# SCH_enigma_2022-11-20.net
KiCad netlist of a schematic drawn in EasyEDA
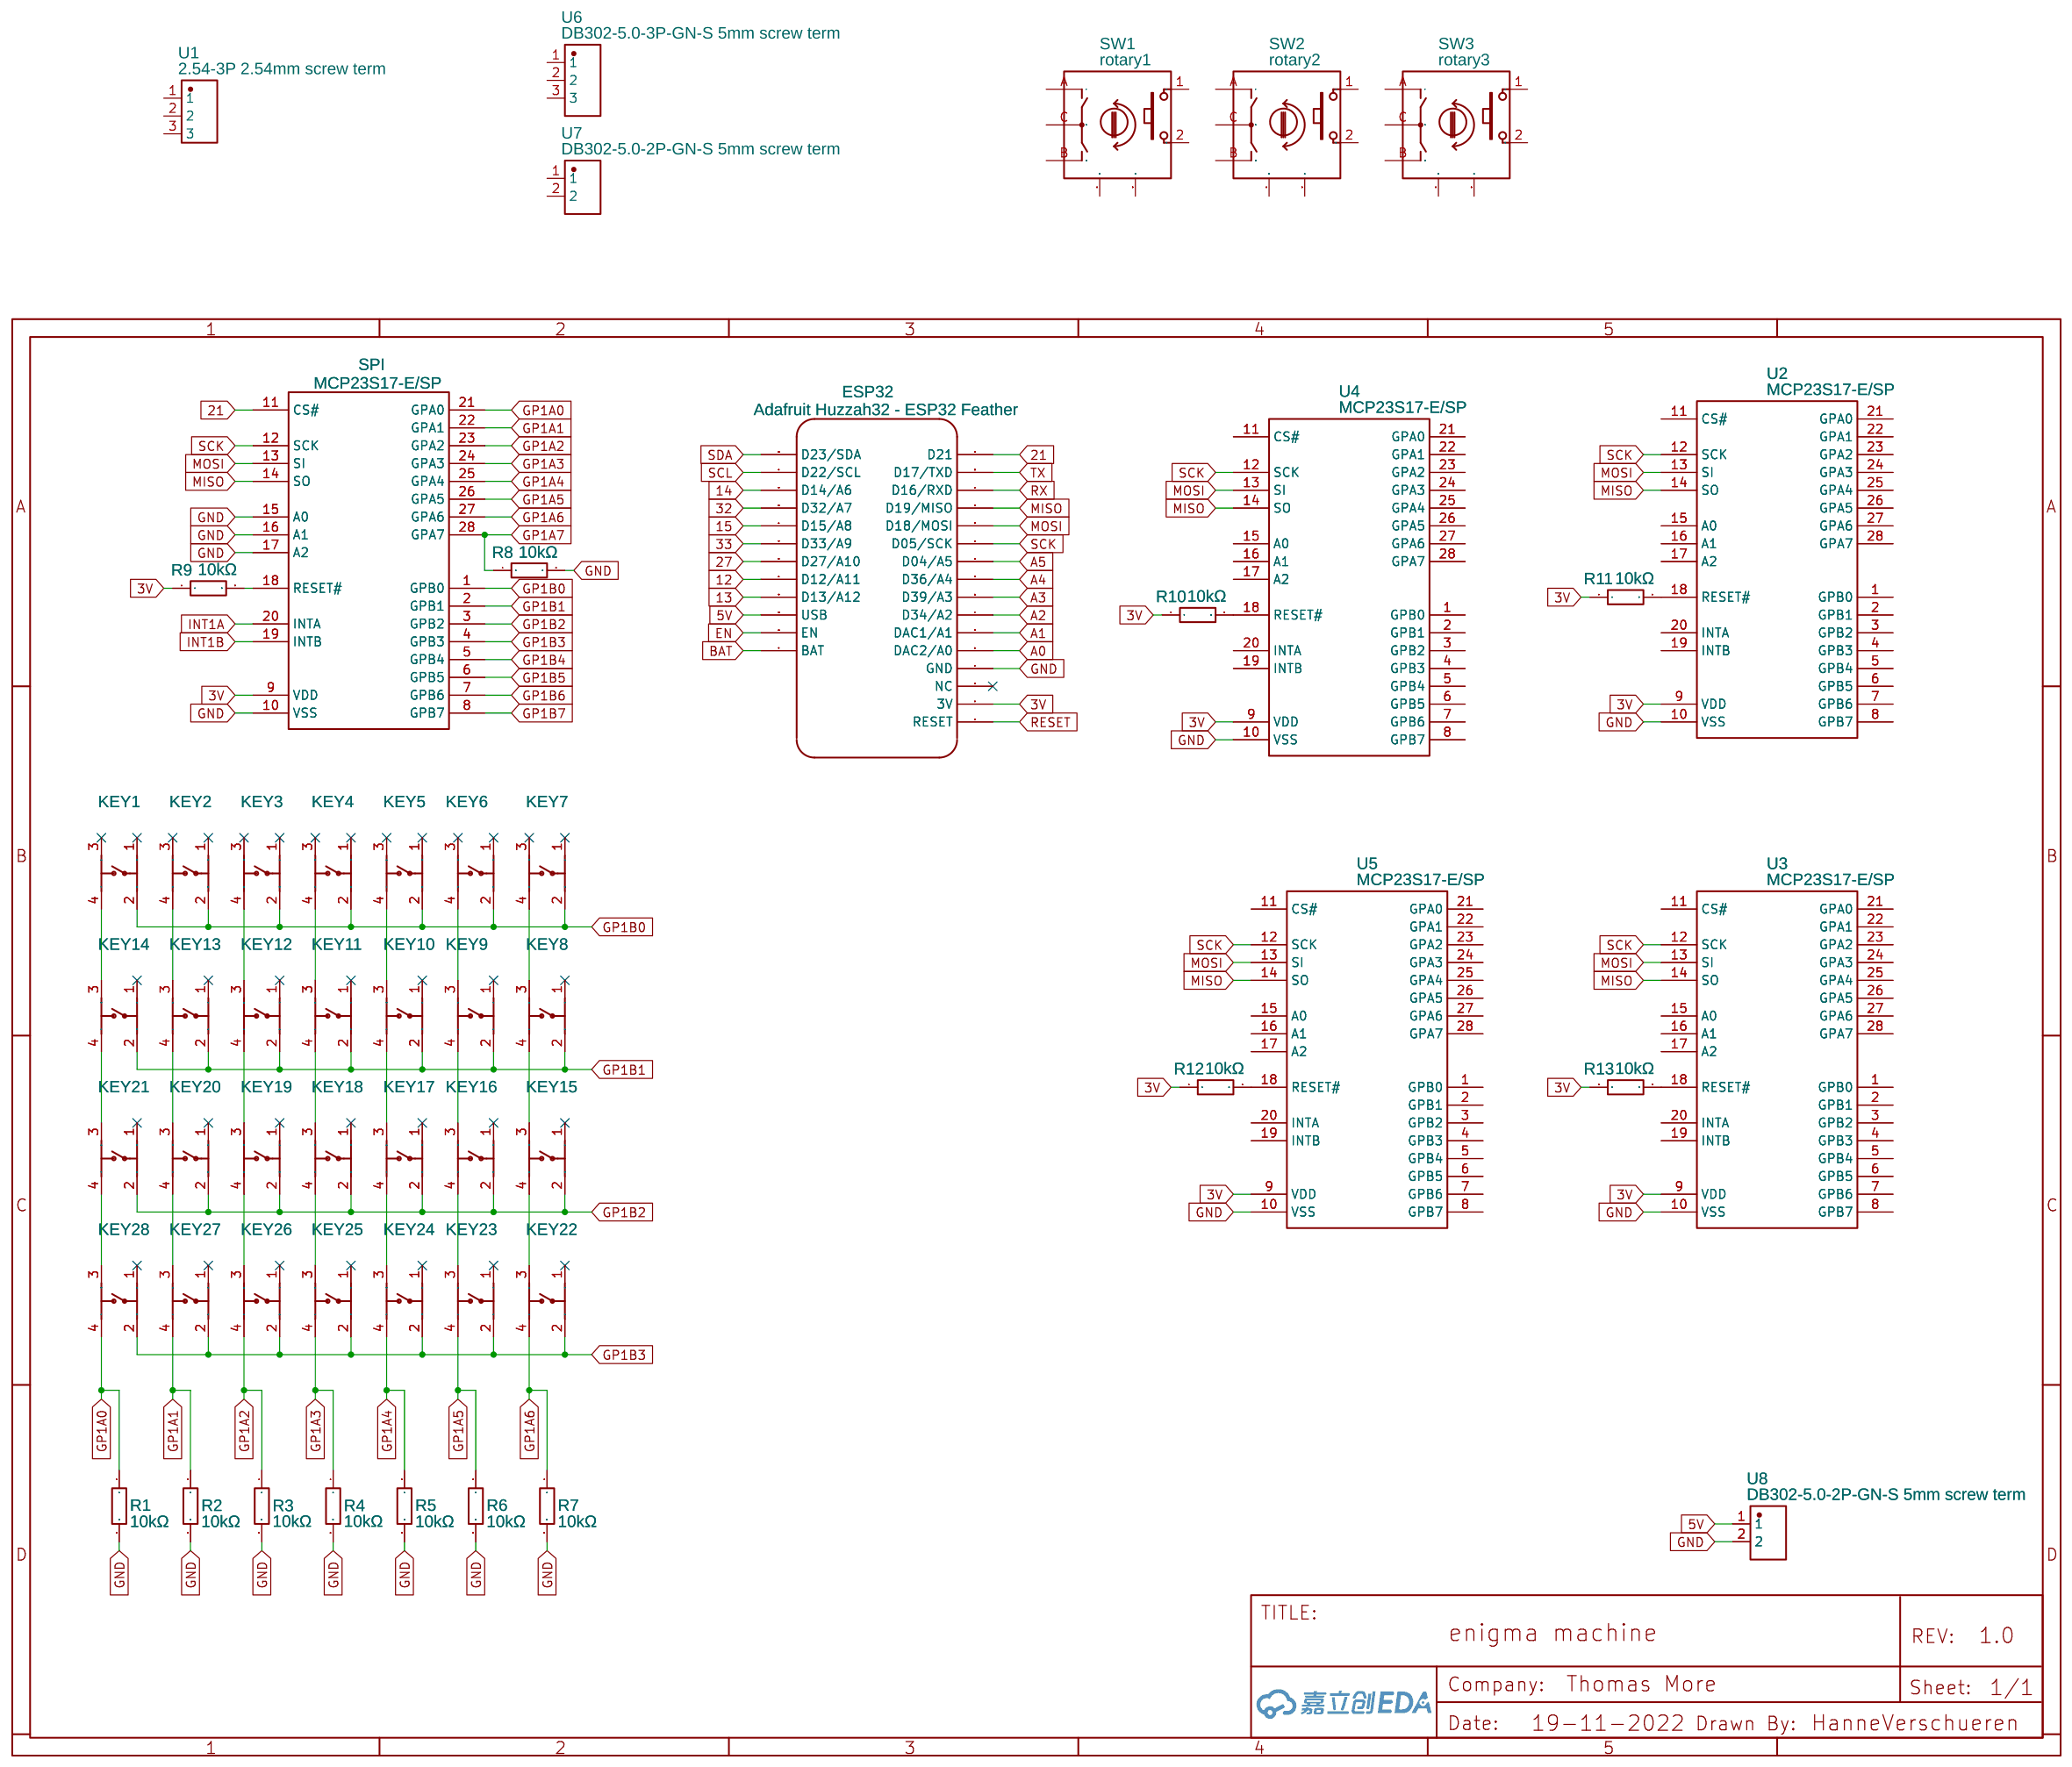
[diagram p0: schematic sheet]

(export (version "E")
  (design (tool "Eeschema 10.0.6"))
  (components
    (comp (ref "ESP32")
      (value "Adafruit Huzzah32 - ESP32 Feather")
      (fields (field (name "BOM_Manufacturer Part") "3405") (field (name "BOM_Supplier Part") "485-3405"))
      (libsource (lib "") (part "Adafruit Huzzah32 - ESP32 Feather"))
    )
    (comp (ref "KEY1")
      (value "12*12*7.3")
      (fields (field (name "BOM_Supplier Part") "C41103"))
      (libsource (lib "") (part "12*12*7.3"))
    )
    (comp (ref "KEY2")
      (value "12*12*7.3")
      (fields (field (name "BOM_Supplier Part") "C41103"))
      (libsource (lib "") (part "12*12*7.3"))
    )
    (comp (ref "KEY3")
      (value "12*12*7.3")
      (fields (field (name "BOM_Supplier Part") "C41103"))
      (libsource (lib "") (part "12*12*7.3"))
    )
    (comp (ref "KEY4")
      (value "12*12*7.3")
      (fields (field (name "BOM_Supplier Part") "C41103"))
      (libsource (lib "") (part "12*12*7.3"))
    )
    (comp (ref "KEY5")
      (value "12*12*7.3")
      (fields (field (name "BOM_Supplier Part") "C41103"))
      (libsource (lib "") (part "12*12*7.3"))
    )
    (comp (ref "KEY6")
      (value "12*12*7.3")
      (fields (field (name "BOM_Supplier Part") "C41103"))
      (libsource (lib "") (part "12*12*7.3"))
    )
    (comp (ref "KEY7")
      (value "12*12*7.3")
      (fields (field (name "BOM_Supplier Part") "C41103"))
      (libsource (lib "") (part "12*12*7.3"))
    )
    (comp (ref "KEY8")
      (value "12*12*7.3")
      (fields (field (name "BOM_Supplier Part") "C41103"))
      (libsource (lib "") (part "12*12*7.3"))
    )
    (comp (ref "KEY9")
      (value "12*12*7.3")
      (fields (field (name "BOM_Supplier Part") "C41103"))
      (libsource (lib "") (part "12*12*7.3"))
    )
    (comp (ref "KEY10")
      (value "12*12*7.3")
      (fields (field (name "BOM_Supplier Part") "C41103"))
      (libsource (lib "") (part "12*12*7.3"))
    )
    (comp (ref "KEY11")
      (value "12*12*7.3")
      (fields (field (name "BOM_Supplier Part") "C41103"))
      (libsource (lib "") (part "12*12*7.3"))
    )
    (comp (ref "KEY12")
      (value "12*12*7.3")
      (fields (field (name "BOM_Supplier Part") "C41103"))
      (libsource (lib "") (part "12*12*7.3"))
    )
    (comp (ref "KEY13")
      (value "12*12*7.3")
      (fields (field (name "BOM_Supplier Part") "C41103"))
      (libsource (lib "") (part "12*12*7.3"))
    )
    (comp (ref "KEY14")
      (value "12*12*7.3")
      (fields (field (name "BOM_Supplier Part") "C41103"))
      (libsource (lib "") (part "12*12*7.3"))
    )
    (comp (ref "KEY15")
      (value "12*12*7.3")
      (fields (field (name "BOM_Supplier Part") "C41103"))
      (libsource (lib "") (part "12*12*7.3"))
    )
    (comp (ref "KEY16")
      (value "12*12*7.3")
      (fields (field (name "BOM_Supplier Part") "C41103"))
      (libsource (lib "") (part "12*12*7.3"))
    )
    (comp (ref "KEY17")
      (value "12*12*7.3")
      (fields (field (name "BOM_Supplier Part") "C41103"))
      (libsource (lib "") (part "12*12*7.3"))
    )
    (comp (ref "KEY18")
      (value "12*12*7.3")
      (fields (field (name "BOM_Supplier Part") "C41103"))
      (libsource (lib "") (part "12*12*7.3"))
    )
    (comp (ref "KEY19")
      (value "12*12*7.3")
      (fields (field (name "BOM_Supplier Part") "C41103"))
      (libsource (lib "") (part "12*12*7.3"))
    )
    (comp (ref "KEY20")
      (value "12*12*7.3")
      (fields (field (name "BOM_Supplier Part") "C41103"))
      (libsource (lib "") (part "12*12*7.3"))
    )
    (comp (ref "KEY21")
      (value "12*12*7.3")
      (fields (field (name "BOM_Supplier Part") "C41103"))
      (libsource (lib "") (part "12*12*7.3"))
    )
    (comp (ref "KEY22")
      (value "12*12*7.3")
      (fields (field (name "BOM_Supplier Part") "C41103"))
      (libsource (lib "") (part "12*12*7.3"))
    )
    (comp (ref "KEY23")
      (value "12*12*7.3")
      (fields (field (name "BOM_Supplier Part") "C41103"))
      (libsource (lib "") (part "12*12*7.3"))
    )
    (comp (ref "KEY24")
      (value "12*12*7.3")
      (fields (field (name "BOM_Supplier Part") "C41103"))
      (libsource (lib "") (part "12*12*7.3"))
    )
    (comp (ref "KEY25")
      (value "12*12*7.3")
      (fields (field (name "BOM_Supplier Part") "C41103"))
      (libsource (lib "") (part "12*12*7.3"))
    )
    (comp (ref "KEY26")
      (value "12*12*7.3")
      (fields (field (name "BOM_Supplier Part") "C41103"))
      (libsource (lib "") (part "12*12*7.3"))
    )
    (comp (ref "KEY27")
      (value "12*12*7.3")
      (fields (field (name "BOM_Supplier Part") "C41103"))
      (libsource (lib "") (part "12*12*7.3"))
    )
    (comp (ref "KEY28")
      (value "12*12*7.3")
      (fields (field (name "BOM_Supplier Part") "C41103"))
      (libsource (lib "") (part "12*12*7.3"))
    )
    (comp (ref "R1")
      (value "10kΩ")
      (fields
        (field (name "BOM_Manufacturer Part") "RS-03K103JT")
        (field (name "BOM_Supplier Part") "C73809")
      )
      (libsource (lib "") (part "RS-03K103JT"))
    )
    (comp (ref "R2")
      (value "10kΩ")
      (fields
        (field (name "BOM_Manufacturer Part") "RS-03K103JT")
        (field (name "BOM_Supplier Part") "C73809")
      )
      (libsource (lib "") (part "RS-03K103JT"))
    )
    (comp (ref "R3")
      (value "10kΩ")
      (fields
        (field (name "BOM_Manufacturer Part") "RS-03K103JT")
        (field (name "BOM_Supplier Part") "C73809")
      )
      (libsource (lib "") (part "RS-03K103JT"))
    )
    (comp (ref "R4")
      (value "10kΩ")
      (fields
        (field (name "BOM_Manufacturer Part") "RS-03K103JT")
        (field (name "BOM_Supplier Part") "C73809")
      )
      (libsource (lib "") (part "RS-03K103JT"))
    )
    (comp (ref "R5")
      (value "10kΩ")
      (fields
        (field (name "BOM_Manufacturer Part") "RS-03K103JT")
        (field (name "BOM_Supplier Part") "C73809")
      )
      (libsource (lib "") (part "RS-03K103JT"))
    )
    (comp (ref "R6")
      (value "10kΩ")
      (fields
        (field (name "BOM_Manufacturer Part") "RS-03K103JT")
        (field (name "BOM_Supplier Part") "C73809")
      )
      (libsource (lib "") (part "RS-03K103JT"))
    )
    (comp (ref "R7")
      (value "10kΩ")
      (fields
        (field (name "BOM_Manufacturer Part") "RS-03K103JT")
        (field (name "BOM_Supplier Part") "C73809")
      )
      (libsource (lib "") (part "RS-03K103JT"))
    )
    (comp (ref "R8")
      (value "10kΩ")
      (fields
        (field (name "BOM_Manufacturer Part") "RS-03K103JT")
        (field (name "BOM_Supplier Part") "C73809")
      )
      (libsource (lib "") (part "RS-03K103JT_1"))
    )
    (comp (ref "R9")
      (value "10kΩ")
      (fields
        (field (name "BOM_Manufacturer Part") "RS-03K103JT")
        (field (name "BOM_Supplier Part") "C73809")
      )
      (libsource (lib "") (part "RS-03K103JT_1"))
    )
    (comp (ref "R10")
      (value "10kΩ")
      (fields
        (field (name "BOM_Manufacturer Part") "RS-03K103JT")
        (field (name "BOM_Supplier Part") "C73809")
      )
      (libsource (lib "") (part "RS-03K103JT_1"))
    )
    (comp (ref "R11")
      (value "10kΩ")
      (fields
        (field (name "BOM_Manufacturer Part") "RS-03K103JT")
        (field (name "BOM_Supplier Part") "C73809")
      )
      (libsource (lib "") (part "RS-03K103JT_1"))
    )
    (comp (ref "R12")
      (value "10kΩ")
      (fields
        (field (name "BOM_Manufacturer Part") "RS-03K103JT")
        (field (name "BOM_Supplier Part") "C73809")
      )
      (libsource (lib "") (part "RS-03K103JT_1"))
    )
    (comp (ref "R13")
      (value "10kΩ")
      (fields
        (field (name "BOM_Manufacturer Part") "RS-03K103JT")
        (field (name "BOM_Supplier Part") "C73809")
      )
      (libsource (lib "") (part "RS-03K103JT_1"))
    )
    (comp (ref "SPI")
      (value "MCP23S17-E/SP")
      (fields (field (name "BOM_Supplier Part") "C148096"))
      (libsource (lib "") (part "MCP23S17-E/SP_1"))
    )
    (comp (ref "SW1")
      (value "rotary1")
      (fields
        (field (name "BOM_Manufacturer Part") "PEC11R-4015F-S0024")
        (field (name "BOM_Supplier Part") "C143789")
      )
      (libsource (lib "") (part "PEC11R-4015F-S0024"))
    )
    (comp (ref "SW2")
      (value "rotary2")
      (fields
        (field (name "BOM_Manufacturer Part") "PEC11R-4015F-S0024")
        (field (name "BOM_Supplier Part") "C143789")
      )
      (libsource (lib "") (part "PEC11R-4015F-S0024"))
    )
    (comp (ref "SW3")
      (value "rotary3")
      (fields
        (field (name "BOM_Manufacturer Part") "PEC11R-4015F-S0024")
        (field (name "BOM_Supplier Part") "C143789")
      )
      (libsource (lib "") (part "PEC11R-4015F-S0024"))
    )
    (comp (ref "U1")
      (value "2.54-3P 2.54mm screw term")
      (fields
        (field (name "BOM_Manufacturer Part") "2.54-3P接线端子")
        (field (name "BOM_Supplier Part") "C68305")
      )
      (libsource (lib "") (part "2.54-3P"))
    )
    (comp (ref "U2")
      (value "MCP23S17-E/SP")
      (fields (field (name "BOM_Supplier Part") "C148096"))
      (libsource (lib "") (part "MCP23S17-E/SP"))
    )
    (comp (ref "U3")
      (value "MCP23S17-E/SP")
      (fields (field (name "BOM_Supplier Part") "C148096"))
      (libsource (lib "") (part "MCP23S17-E/SP"))
    )
    (comp (ref "U4")
      (value "MCP23S17-E/SP")
      (fields (field (name "BOM_Supplier Part") "C148096"))
      (libsource (lib "") (part "MCP23S17-E/SP"))
    )
    (comp (ref "U5")
      (value "MCP23S17-E/SP")
      (fields (field (name "BOM_Supplier Part") "C148096"))
      (libsource (lib "") (part "MCP23S17-E/SP"))
    )
    (comp (ref "U6")
      (value "DB302-5.0-3P-GN-S 5mm screw term")
      (fields
        (field (name "BOM_Manufacturer Part") "DB302-5.0-3P-GN-S")
        (field (name "BOM_Supplier Part") "C2997276")
      )
      (libsource (lib "") (part "DB302-5.0-3P-GN-S"))
    )
    (comp (ref "U7")
      (value "DB302-5.0-2P-GN-S 5mm screw term")
      (fields
        (field (name "BOM_Manufacturer Part") "DB302-5.0-2P-GN-S")
        (field (name "BOM_Supplier Part") "C2997275")
      )
      (libsource (lib "") (part "DB302-5.0-2P-GN-S"))
    )
    (comp (ref "U8")
      (value "DB302-5.0-2P-GN-S 5mm screw term")
      (fields
        (field (name "BOM_Manufacturer Part") "DB302-5.0-2P-GN-S")
        (field (name "BOM_Supplier Part") "C2997275")
      )
      (libsource (lib "") (part "DB302-5.0-2P-GN-S"))
    )
  )
  (nets
    (net (code "1") (name "3V") (class "Default")
      (node (ref "ESP32") (pin "2") (pinfunction "3V_2") (pintype "unspecified"))
      (node (ref "R10") (pin "1") (pinfunction "1_1") (pintype "input"))
      (node (ref "R11") (pin "1") (pinfunction "1_1") (pintype "input"))
      (node (ref "R12") (pin "1") (pinfunction "1_1") (pintype "input"))
      (node (ref "R13") (pin "1") (pinfunction "1_1") (pintype "input"))
      (node (ref "R9") (pin "1") (pinfunction "1_1") (pintype "input"))
      (node (ref "SPI") (pin "9") (pinfunction "VDD_9") (pintype "passive"))
      (node (ref "U2") (pin "9") (pinfunction "VDD_9") (pintype "passive"))
      (node (ref "U3") (pin "9") (pinfunction "VDD_9") (pintype "passive"))
      (node (ref "U4") (pin "9") (pinfunction "VDD_9") (pintype "passive"))
      (node (ref "U5") (pin "9") (pinfunction "VDD_9") (pintype "passive"))
    )
    (net (code "2") (name "5V") (class "Default")
      (node (ref "ESP32") (pin "19") (pinfunction "USB_19") (pintype "unspecified"))
      (node (ref "U8") (pin "1") (pinfunction "1_1") (pintype "unspecified"))
    )
    (net (code "3") (name "12") (class "Default")
      (node (ref "ESP32") (pin "21") (pinfunction "D12/A11_21") (pintype "unspecified"))
    )
    (net (code "4") (name "13") (class "Default")
      (node (ref "ESP32") (pin "20") (pinfunction "D13/A12_20") (pintype "unspecified"))
    )
    (net (code "5") (name "14") (class "Default")
      (node (ref "ESP32") (pin "26") (pinfunction "D14/A6_26") (pintype "unspecified"))
    )
    (net (code "6") (name "15") (class "Default")
      (node (ref "ESP32") (pin "24") (pinfunction "D15/A8_24") (pintype "unspecified"))
    )
    (net (code "7") (name "21") (class "Default")
      (node (ref "ESP32") (pin "16") (pinfunction "D21_16") (pintype "unspecified"))
      (node (ref "SPI") (pin "11") (pinfunction "CS#_11") (pintype "unspecified"))
    )
    (net (code "8") (name "27") (class "Default")
      (node (ref "ESP32") (pin "22") (pinfunction "D27/A10_22") (pintype "unspecified"))
    )
    (net (code "9") (name "32") (class "Default")
      (node (ref "ESP32") (pin "25") (pinfunction "D32/A7_25") (pintype "unspecified"))
    )
    (net (code "10") (name "33") (class "Default")
      (node (ref "ESP32") (pin "23") (pinfunction "D33/A9_23") (pintype "unspecified"))
    )
    (net (code "11") (name "A0") (class "Default")
      (node (ref "ESP32") (pin "5") (pinfunction "DAC2/A0_5") (pintype "unspecified"))
    )
    (net (code "12") (name "A1") (class "Default")
      (node (ref "ESP32") (pin "6") (pinfunction "DAC1/A1_6") (pintype "unspecified"))
    )
    (net (code "13") (name "A2") (class "Default")
      (node (ref "ESP32") (pin "7") (pinfunction "D34/A2_7") (pintype "unspecified"))
    )
    (net (code "14") (name "A3") (class "Default")
      (node (ref "ESP32") (pin "8") (pinfunction "D39/A3_8") (pintype "unspecified"))
    )
    (net (code "15") (name "A4") (class "Default")
      (node (ref "ESP32") (pin "9") (pinfunction "D36/A4_9") (pintype "unspecified"))
    )
    (net (code "16") (name "A5") (class "Default")
      (node (ref "ESP32") (pin "10") (pinfunction "D04/A5_10") (pintype "unspecified"))
    )
    (net (code "17") (name "BAT") (class "Default")
      (node (ref "ESP32") (pin "17") (pinfunction "BAT_17") (pintype "unspecified"))
    )
    (net (code "18") (name "EN") (class "Default")
      (node (ref "ESP32") (pin "18") (pinfunction "EN_18") (pintype "unspecified"))
    )
    (net (code "19") (name "GND") (class "Default")
      (node (ref "ESP32") (pin "4") (pinfunction "GND_4") (pintype "unspecified"))
      (node (ref "R1") (pin "2") (pinfunction "2_2") (pintype "input"))
      (node (ref "R2") (pin "2") (pinfunction "2_2") (pintype "input"))
      (node (ref "R3") (pin "2") (pinfunction "2_2") (pintype "input"))
      (node (ref "R4") (pin "2") (pinfunction "2_2") (pintype "input"))
      (node (ref "R5") (pin "2") (pinfunction "2_2") (pintype "input"))
      (node (ref "R6") (pin "2") (pinfunction "2_2") (pintype "input"))
      (node (ref "R7") (pin "2") (pinfunction "2_2") (pintype "input"))
      (node (ref "R8") (pin "2") (pinfunction "2_2") (pintype "input"))
      (node (ref "SPI") (pin "10") (pinfunction "VSS_10") (pintype "passive"))
      (node (ref "SPI") (pin "15") (pinfunction "A0_15") (pintype "unspecified"))
      (node (ref "SPI") (pin "16") (pinfunction "A1_16") (pintype "unspecified"))
      (node (ref "SPI") (pin "17") (pinfunction "A2_17") (pintype "unspecified"))
      (node (ref "U2") (pin "10") (pinfunction "VSS_10") (pintype "passive"))
      (node (ref "U3") (pin "10") (pinfunction "VSS_10") (pintype "passive"))
      (node (ref "U4") (pin "10") (pinfunction "VSS_10") (pintype "passive"))
      (node (ref "U5") (pin "10") (pinfunction "VSS_10") (pintype "passive"))
      (node (ref "U8") (pin "2") (pinfunction "2_2") (pintype "unspecified"))
    )
    (net (code "20") (name "GP1A0") (class "Default")
      (node (ref "KEY28") (pin "4") (pinfunction "4_4") (pintype "unspecified"))
      (node (ref "R1") (pin "1") (pinfunction "1_1") (pintype "input"))
      (node (ref "SPI") (pin "21") (pinfunction "GPA0_21") (pintype "bidirectional"))
    )
    (net (code "21") (name "GP1A1") (class "Default")
      (node (ref "KEY27") (pin "4") (pinfunction "4_4") (pintype "unspecified"))
      (node (ref "R2") (pin "1") (pinfunction "1_1") (pintype "input"))
      (node (ref "SPI") (pin "22") (pinfunction "GPA1_22") (pintype "bidirectional"))
    )
    (net (code "22") (name "GP1A2") (class "Default")
      (node (ref "KEY26") (pin "4") (pinfunction "4_4") (pintype "unspecified"))
      (node (ref "R3") (pin "1") (pinfunction "1_1") (pintype "input"))
      (node (ref "SPI") (pin "23") (pinfunction "GPA2_23") (pintype "bidirectional"))
    )
    (net (code "23") (name "GP1A3") (class "Default")
      (node (ref "KEY25") (pin "4") (pinfunction "4_4") (pintype "unspecified"))
      (node (ref "R4") (pin "1") (pinfunction "1_1") (pintype "input"))
      (node (ref "SPI") (pin "24") (pinfunction "GPA3_24") (pintype "bidirectional"))
    )
    (net (code "24") (name "GP1A4") (class "Default")
      (node (ref "KEY24") (pin "4") (pinfunction "4_4") (pintype "unspecified"))
      (node (ref "R5") (pin "1") (pinfunction "1_1") (pintype "input"))
      (node (ref "SPI") (pin "25") (pinfunction "GPA4_25") (pintype "bidirectional"))
    )
    (net (code "25") (name "GP1A5") (class "Default")
      (node (ref "KEY23") (pin "4") (pinfunction "4_4") (pintype "unspecified"))
      (node (ref "R6") (pin "1") (pinfunction "1_1") (pintype "input"))
      (node (ref "SPI") (pin "26") (pinfunction "GPA5_26") (pintype "bidirectional"))
    )
    (net (code "26") (name "GP1A6") (class "Default")
      (node (ref "KEY22") (pin "4") (pinfunction "4_4") (pintype "unspecified"))
      (node (ref "R7") (pin "1") (pinfunction "1_1") (pintype "input"))
      (node (ref "SPI") (pin "27") (pinfunction "GPA6_27") (pintype "bidirectional"))
    )
    (net (code "27") (name "GP1A7") (class "Default")
      (node (ref "R8") (pin "1") (pinfunction "1_1") (pintype "input"))
      (node (ref "SPI") (pin "28") (pinfunction "GPA7_28") (pintype "bidirectional"))
    )
    (net (code "28") (name "GP1B0") (class "Default")
      (node (ref "KEY1") (pin "2") (pinfunction "2_2") (pintype "unspecified"))
      (node (ref "KEY2") (pin "2") (pinfunction "2_2") (pintype "unspecified"))
      (node (ref "KEY3") (pin "2") (pinfunction "2_2") (pintype "unspecified"))
      (node (ref "KEY4") (pin "2") (pinfunction "2_2") (pintype "unspecified"))
      (node (ref "KEY5") (pin "2") (pinfunction "2_2") (pintype "unspecified"))
      (node (ref "KEY6") (pin "2") (pinfunction "2_2") (pintype "unspecified"))
      (node (ref "KEY7") (pin "2") (pinfunction "2_2") (pintype "unspecified"))
      (node (ref "SPI") (pin "1") (pinfunction "GPB0_1") (pintype "bidirectional"))
    )
    (net (code "29") (name "GP1B1") (class "Default")
      (node (ref "KEY10") (pin "2") (pinfunction "2_2") (pintype "unspecified"))
      (node (ref "KEY11") (pin "2") (pinfunction "2_2") (pintype "unspecified"))
      (node (ref "KEY12") (pin "2") (pinfunction "2_2") (pintype "unspecified"))
      (node (ref "KEY13") (pin "2") (pinfunction "2_2") (pintype "unspecified"))
      (node (ref "KEY14") (pin "2") (pinfunction "2_2") (pintype "unspecified"))
      (node (ref "KEY8") (pin "2") (pinfunction "2_2") (pintype "unspecified"))
      (node (ref "KEY9") (pin "2") (pinfunction "2_2") (pintype "unspecified"))
      (node (ref "SPI") (pin "2") (pinfunction "GPB1_2") (pintype "bidirectional"))
    )
    (net (code "30") (name "GP1B2") (class "Default")
      (node (ref "KEY15") (pin "2") (pinfunction "2_2") (pintype "unspecified"))
      (node (ref "KEY16") (pin "2") (pinfunction "2_2") (pintype "unspecified"))
      (node (ref "KEY17") (pin "2") (pinfunction "2_2") (pintype "unspecified"))
      (node (ref "KEY18") (pin "2") (pinfunction "2_2") (pintype "unspecified"))
      (node (ref "KEY19") (pin "2") (pinfunction "2_2") (pintype "unspecified"))
      (node (ref "KEY20") (pin "2") (pinfunction "2_2") (pintype "unspecified"))
      (node (ref "KEY21") (pin "2") (pinfunction "2_2") (pintype "unspecified"))
      (node (ref "SPI") (pin "3") (pinfunction "GPB2_3") (pintype "bidirectional"))
    )
    (net (code "31") (name "GP1B3") (class "Default")
      (node (ref "KEY22") (pin "2") (pinfunction "2_2") (pintype "unspecified"))
      (node (ref "KEY23") (pin "2") (pinfunction "2_2") (pintype "unspecified"))
      (node (ref "KEY24") (pin "2") (pinfunction "2_2") (pintype "unspecified"))
      (node (ref "KEY25") (pin "2") (pinfunction "2_2") (pintype "unspecified"))
      (node (ref "KEY26") (pin "2") (pinfunction "2_2") (pintype "unspecified"))
      (node (ref "KEY27") (pin "2") (pinfunction "2_2") (pintype "unspecified"))
      (node (ref "KEY28") (pin "2") (pinfunction "2_2") (pintype "unspecified"))
      (node (ref "SPI") (pin "4") (pinfunction "GPB3_4") (pintype "bidirectional"))
    )
    (net (code "32") (name "GP1B4") (class "Default")
      (node (ref "SPI") (pin "5") (pinfunction "GPB4_5") (pintype "bidirectional"))
    )
    (net (code "33") (name "GP1B5") (class "Default")
      (node (ref "SPI") (pin "6") (pinfunction "GPB5_6") (pintype "bidirectional"))
    )
    (net (code "34") (name "GP1B6") (class "Default")
      (node (ref "SPI") (pin "7") (pinfunction "GPB6_7") (pintype "bidirectional"))
    )
    (net (code "35") (name "GP1B7") (class "Default")
      (node (ref "SPI") (pin "8") (pinfunction "GPB7_8") (pintype "bidirectional"))
    )
    (net (code "36") (name "INT1A") (class "Default")
      (node (ref "SPI") (pin "20") (pinfunction "INTA_20") (pintype "unspecified"))
    )
    (net (code "37") (name "INT1B") (class "Default")
      (node (ref "SPI") (pin "19") (pinfunction "INTB_19") (pintype "unspecified"))
    )
    (net (code "38") (name "MISO") (class "Default")
      (node (ref "ESP32") (pin "13") (pinfunction "D19/MISO_13") (pintype "unspecified"))
      (node (ref "SPI") (pin "14") (pinfunction "SO_14") (pintype "unspecified"))
      (node (ref "U2") (pin "14") (pinfunction "SO_14") (pintype "unspecified"))
      (node (ref "U3") (pin "14") (pinfunction "SO_14") (pintype "unspecified"))
      (node (ref "U4") (pin "14") (pinfunction "SO_14") (pintype "unspecified"))
      (node (ref "U5") (pin "14") (pinfunction "SO_14") (pintype "unspecified"))
    )
    (net (code "39") (name "MOSI") (class "Default")
      (node (ref "ESP32") (pin "12") (pinfunction "D18/MOSI_12") (pintype "unspecified"))
      (node (ref "SPI") (pin "13") (pinfunction "SI_13") (pintype "unspecified"))
      (node (ref "U2") (pin "13") (pinfunction "SI_13") (pintype "unspecified"))
      (node (ref "U3") (pin "13") (pinfunction "SI_13") (pintype "unspecified"))
      (node (ref "U4") (pin "13") (pinfunction "SI_13") (pintype "unspecified"))
      (node (ref "U5") (pin "13") (pinfunction "SI_13") (pintype "unspecified"))
    )
    (net (code "40") (name "Net-(KEY1-Pad4)") (class "Default")
      (node (ref "KEY1") (pin "4") (pinfunction "4_4") (pintype "unspecified"))
      (node (ref "KEY14") (pin "3") (pinfunction "3_3") (pintype "unspecified"))
    )
    (net (code "41") (name "Net-(KEY6-Pad4)") (class "Default")
      (node (ref "KEY6") (pin "4") (pinfunction "4_4") (pintype "unspecified"))
      (node (ref "KEY9") (pin "3") (pinfunction "3_3") (pintype "unspecified"))
    )
    (net (code "42") (name "Net-(KEY7-Pad4)") (class "Default")
      (node (ref "KEY7") (pin "4") (pinfunction "4_4") (pintype "unspecified"))
      (node (ref "KEY8") (pin "3") (pinfunction "3_3") (pintype "unspecified"))
    )
    (net (code "43") (name "Net-(KEY10-Pad3)") (class "Default")
      (node (ref "KEY10") (pin "3") (pinfunction "3_3") (pintype "unspecified"))
      (node (ref "KEY5") (pin "4") (pinfunction "4_4") (pintype "unspecified"))
    )
    (net (code "44") (name "Net-(KEY10-Pad4)") (class "Default")
      (node (ref "KEY10") (pin "4") (pinfunction "4_4") (pintype "unspecified"))
      (node (ref "KEY17") (pin "3") (pinfunction "3_3") (pintype "unspecified"))
    )
    (net (code "45") (name "Net-(KEY11-Pad3)") (class "Default")
      (node (ref "KEY11") (pin "3") (pinfunction "3_3") (pintype "unspecified"))
      (node (ref "KEY4") (pin "4") (pinfunction "4_4") (pintype "unspecified"))
    )
    (net (code "46") (name "Net-(KEY11-Pad4)") (class "Default")
      (node (ref "KEY11") (pin "4") (pinfunction "4_4") (pintype "unspecified"))
      (node (ref "KEY18") (pin "3") (pinfunction "3_3") (pintype "unspecified"))
    )
    (net (code "47") (name "Net-(KEY12-Pad3)") (class "Default")
      (node (ref "KEY12") (pin "3") (pinfunction "3_3") (pintype "unspecified"))
      (node (ref "KEY3") (pin "4") (pinfunction "4_4") (pintype "unspecified"))
    )
    (net (code "48") (name "Net-(KEY12-Pad4)") (class "Default")
      (node (ref "KEY12") (pin "4") (pinfunction "4_4") (pintype "unspecified"))
      (node (ref "KEY19") (pin "3") (pinfunction "3_3") (pintype "unspecified"))
    )
    (net (code "49") (name "Net-(KEY13-Pad3)") (class "Default")
      (node (ref "KEY13") (pin "3") (pinfunction "3_3") (pintype "unspecified"))
      (node (ref "KEY2") (pin "4") (pinfunction "4_4") (pintype "unspecified"))
    )
    (net (code "50") (name "Net-(KEY13-Pad4)") (class "Default")
      (node (ref "KEY13") (pin "4") (pinfunction "4_4") (pintype "unspecified"))
      (node (ref "KEY20") (pin "3") (pinfunction "3_3") (pintype "unspecified"))
    )
    (net (code "51") (name "Net-(KEY14-Pad4)") (class "Default")
      (node (ref "KEY14") (pin "4") (pinfunction "4_4") (pintype "unspecified"))
      (node (ref "KEY21") (pin "3") (pinfunction "3_3") (pintype "unspecified"))
    )
    (net (code "52") (name "Net-(KEY15-Pad3)") (class "Default")
      (node (ref "KEY15") (pin "3") (pinfunction "3_3") (pintype "unspecified"))
      (node (ref "KEY8") (pin "4") (pinfunction "4_4") (pintype "unspecified"))
    )
    (net (code "53") (name "Net-(KEY15-Pad4)") (class "Default")
      (node (ref "KEY15") (pin "4") (pinfunction "4_4") (pintype "unspecified"))
      (node (ref "KEY22") (pin "3") (pinfunction "3_3") (pintype "unspecified"))
    )
    (net (code "54") (name "Net-(KEY16-Pad3)") (class "Default")
      (node (ref "KEY16") (pin "3") (pinfunction "3_3") (pintype "unspecified"))
      (node (ref "KEY9") (pin "4") (pinfunction "4_4") (pintype "unspecified"))
    )
    (net (code "55") (name "Net-(KEY16-Pad4)") (class "Default")
      (node (ref "KEY16") (pin "4") (pinfunction "4_4") (pintype "unspecified"))
      (node (ref "KEY23") (pin "3") (pinfunction "3_3") (pintype "unspecified"))
    )
    (net (code "56") (name "Net-(KEY17-Pad4)") (class "Default")
      (node (ref "KEY17") (pin "4") (pinfunction "4_4") (pintype "unspecified"))
      (node (ref "KEY24") (pin "3") (pinfunction "3_3") (pintype "unspecified"))
    )
    (net (code "57") (name "Net-(KEY18-Pad4)") (class "Default")
      (node (ref "KEY18") (pin "4") (pinfunction "4_4") (pintype "unspecified"))
      (node (ref "KEY25") (pin "3") (pinfunction "3_3") (pintype "unspecified"))
    )
    (net (code "58") (name "Net-(KEY19-Pad4)") (class "Default")
      (node (ref "KEY19") (pin "4") (pinfunction "4_4") (pintype "unspecified"))
      (node (ref "KEY26") (pin "3") (pinfunction "3_3") (pintype "unspecified"))
    )
    (net (code "59") (name "Net-(KEY20-Pad4)") (class "Default")
      (node (ref "KEY20") (pin "4") (pinfunction "4_4") (pintype "unspecified"))
      (node (ref "KEY27") (pin "3") (pinfunction "3_3") (pintype "unspecified"))
    )
    (net (code "60") (name "Net-(KEY21-Pad4)") (class "Default")
      (node (ref "KEY21") (pin "4") (pinfunction "4_4") (pintype "unspecified"))
      (node (ref "KEY28") (pin "3") (pinfunction "3_3") (pintype "unspecified"))
    )
    (net (code "61") (name "Net-(SPI-RESET#)") (class "Default")
      (node (ref "R9") (pin "2") (pinfunction "2_2") (pintype "input"))
      (node (ref "SPI") (pin "18") (pinfunction "RESET#_18") (pintype "unspecified"))
    )
    (net (code "62") (name "Net-(U2-RESET#)") (class "Default")
      (node (ref "R11") (pin "2") (pinfunction "2_2") (pintype "input"))
      (node (ref "U2") (pin "18") (pinfunction "RESET#_18") (pintype "unspecified"))
    )
    (net (code "63") (name "Net-(U3-RESET#)") (class "Default")
      (node (ref "R13") (pin "2") (pinfunction "2_2") (pintype "input"))
      (node (ref "U3") (pin "18") (pinfunction "RESET#_18") (pintype "unspecified"))
    )
    (net (code "64") (name "Net-(U4-RESET#)") (class "Default")
      (node (ref "R10") (pin "2") (pinfunction "2_2") (pintype "input"))
      (node (ref "U4") (pin "18") (pinfunction "RESET#_18") (pintype "unspecified"))
    )
    (net (code "65") (name "Net-(U5-RESET#)") (class "Default")
      (node (ref "R12") (pin "2") (pinfunction "2_2") (pintype "input"))
      (node (ref "U5") (pin "18") (pinfunction "RESET#_18") (pintype "unspecified"))
    )
    (net (code "66") (name "RESET") (class "Default")
      (node (ref "ESP32") (pin "1") (pinfunction "RESET_1") (pintype "unspecified"))
    )
    (net (code "67") (name "RX") (class "Default")
      (node (ref "ESP32") (pin "14") (pinfunction "D16/RXD_14") (pintype "unspecified"))
    )
    (net (code "68") (name "SCK") (class "Default")
      (node (ref "ESP32") (pin "11") (pinfunction "D05/SCK_11") (pintype "unspecified"))
      (node (ref "SPI") (pin "12") (pinfunction "SCK_12") (pintype "unspecified"))
      (node (ref "U2") (pin "12") (pinfunction "SCK_12") (pintype "unspecified"))
      (node (ref "U3") (pin "12") (pinfunction "SCK_12") (pintype "unspecified"))
      (node (ref "U4") (pin "12") (pinfunction "SCK_12") (pintype "unspecified"))
      (node (ref "U5") (pin "12") (pinfunction "SCK_12") (pintype "unspecified"))
    )
    (net (code "69") (name "SCL") (class "Default")
      (node (ref "ESP32") (pin "27") (pinfunction "D22/SCL_27") (pintype "unspecified"))
    )
    (net (code "70") (name "SDA") (class "Default")
      (node (ref "ESP32") (pin "28") (pinfunction "D23/SDA_28") (pintype "unspecified"))
    )
    (net (code "71") (name "TX") (class "Default")
      (node (ref "ESP32") (pin "15") (pinfunction "D17/TXD_15") (pintype "unspecified"))
    )
    (net (code "72") (name "unconnected-(ESP32-NC-Pad3)") (class "Default")
      (node (ref "ESP32") (pin "3") (pinfunction "NC_3") (pintype "unspecified+no_connect"))
    )
    (net (code "73") (name "unconnected-(KEY1-Pad1)") (class "Default")
      (node (ref "KEY1") (pin "1") (pinfunction "1_1") (pintype "unspecified+no_connect"))
    )
    (net (code "74") (name "unconnected-(KEY1-Pad3)") (class "Default")
      (node (ref "KEY1") (pin "3") (pinfunction "3_3") (pintype "unspecified+no_connect"))
    )
    (net (code "75") (name "unconnected-(KEY2-Pad1)") (class "Default")
      (node (ref "KEY2") (pin "1") (pinfunction "1_1") (pintype "unspecified+no_connect"))
    )
    (net (code "76") (name "unconnected-(KEY2-Pad3)") (class "Default")
      (node (ref "KEY2") (pin "3") (pinfunction "3_3") (pintype "unspecified+no_connect"))
    )
    (net (code "77") (name "unconnected-(KEY3-Pad1)") (class "Default")
      (node (ref "KEY3") (pin "1") (pinfunction "1_1") (pintype "unspecified+no_connect"))
    )
    (net (code "78") (name "unconnected-(KEY3-Pad3)") (class "Default")
      (node (ref "KEY3") (pin "3") (pinfunction "3_3") (pintype "unspecified+no_connect"))
    )
    (net (code "79") (name "unconnected-(KEY4-Pad1)") (class "Default")
      (node (ref "KEY4") (pin "1") (pinfunction "1_1") (pintype "unspecified+no_connect"))
    )
    (net (code "80") (name "unconnected-(KEY4-Pad3)") (class "Default")
      (node (ref "KEY4") (pin "3") (pinfunction "3_3") (pintype "unspecified+no_connect"))
    )
    (net (code "81") (name "unconnected-(KEY5-Pad1)") (class "Default")
      (node (ref "KEY5") (pin "1") (pinfunction "1_1") (pintype "unspecified+no_connect"))
    )
    (net (code "82") (name "unconnected-(KEY5-Pad3)") (class "Default")
      (node (ref "KEY5") (pin "3") (pinfunction "3_3") (pintype "unspecified+no_connect"))
    )
    (net (code "83") (name "unconnected-(KEY6-Pad1)") (class "Default")
      (node (ref "KEY6") (pin "1") (pinfunction "1_1") (pintype "unspecified+no_connect"))
    )
    (net (code "84") (name "unconnected-(KEY6-Pad3)") (class "Default")
      (node (ref "KEY6") (pin "3") (pinfunction "3_3") (pintype "unspecified+no_connect"))
    )
    (net (code "85") (name "unconnected-(KEY7-Pad1)") (class "Default")
      (node (ref "KEY7") (pin "1") (pinfunction "1_1") (pintype "unspecified+no_connect"))
    )
    (net (code "86") (name "unconnected-(KEY7-Pad3)") (class "Default")
      (node (ref "KEY7") (pin "3") (pinfunction "3_3") (pintype "unspecified+no_connect"))
    )
    (net (code "87") (name "unconnected-(KEY8-Pad1)") (class "Default")
      (node (ref "KEY8") (pin "1") (pinfunction "1_1") (pintype "unspecified+no_connect"))
    )
    (net (code "88") (name "unconnected-(KEY9-Pad1)") (class "Default")
      (node (ref "KEY9") (pin "1") (pinfunction "1_1") (pintype "unspecified+no_connect"))
    )
    (net (code "89") (name "unconnected-(KEY10-Pad1)") (class "Default")
      (node (ref "KEY10") (pin "1") (pinfunction "1_1") (pintype "unspecified+no_connect"))
    )
    (net (code "90") (name "unconnected-(KEY11-Pad1)") (class "Default")
      (node (ref "KEY11") (pin "1") (pinfunction "1_1") (pintype "unspecified+no_connect"))
    )
    (net (code "91") (name "unconnected-(KEY12-Pad1)") (class "Default")
      (node (ref "KEY12") (pin "1") (pinfunction "1_1") (pintype "unspecified+no_connect"))
    )
    (net (code "92") (name "unconnected-(KEY13-Pad1)") (class "Default")
      (node (ref "KEY13") (pin "1") (pinfunction "1_1") (pintype "unspecified+no_connect"))
    )
    (net (code "93") (name "unconnected-(KEY14-Pad1)") (class "Default")
      (node (ref "KEY14") (pin "1") (pinfunction "1_1") (pintype "unspecified+no_connect"))
    )
    (net (code "94") (name "unconnected-(KEY15-Pad1)") (class "Default")
      (node (ref "KEY15") (pin "1") (pinfunction "1_1") (pintype "unspecified+no_connect"))
    )
    (net (code "95") (name "unconnected-(KEY16-Pad1)") (class "Default")
      (node (ref "KEY16") (pin "1") (pinfunction "1_1") (pintype "unspecified+no_connect"))
    )
    (net (code "96") (name "unconnected-(KEY17-Pad1)") (class "Default")
      (node (ref "KEY17") (pin "1") (pinfunction "1_1") (pintype "unspecified+no_connect"))
    )
    (net (code "97") (name "unconnected-(KEY18-Pad1)") (class "Default")
      (node (ref "KEY18") (pin "1") (pinfunction "1_1") (pintype "unspecified+no_connect"))
    )
    (net (code "98") (name "unconnected-(KEY19-Pad1)") (class "Default")
      (node (ref "KEY19") (pin "1") (pinfunction "1_1") (pintype "unspecified+no_connect"))
    )
    (net (code "99") (name "unconnected-(KEY20-Pad1)") (class "Default")
      (node (ref "KEY20") (pin "1") (pinfunction "1_1") (pintype "unspecified+no_connect"))
    )
    (net (code "100") (name "unconnected-(KEY21-Pad1)") (class "Default")
      (node (ref "KEY21") (pin "1") (pinfunction "1_1") (pintype "unspecified+no_connect"))
    )
    (net (code "101") (name "unconnected-(KEY22-Pad1)") (class "Default")
      (node (ref "KEY22") (pin "1") (pinfunction "1_1") (pintype "unspecified+no_connect"))
    )
    (net (code "102") (name "unconnected-(KEY23-Pad1)") (class "Default")
      (node (ref "KEY23") (pin "1") (pinfunction "1_1") (pintype "unspecified+no_connect"))
    )
    (net (code "103") (name "unconnected-(KEY24-Pad1)") (class "Default")
      (node (ref "KEY24") (pin "1") (pinfunction "1_1") (pintype "unspecified+no_connect"))
    )
    (net (code "104") (name "unconnected-(KEY25-Pad1)") (class "Default")
      (node (ref "KEY25") (pin "1") (pinfunction "1_1") (pintype "unspecified+no_connect"))
    )
    (net (code "105") (name "unconnected-(KEY26-Pad1)") (class "Default")
      (node (ref "KEY26") (pin "1") (pinfunction "1_1") (pintype "unspecified+no_connect"))
    )
    (net (code "106") (name "unconnected-(KEY27-Pad1)") (class "Default")
      (node (ref "KEY27") (pin "1") (pinfunction "1_1") (pintype "unspecified+no_connect"))
    )
    (net (code "107") (name "unconnected-(KEY28-Pad1)") (class "Default")
      (node (ref "KEY28") (pin "1") (pinfunction "1_1") (pintype "unspecified+no_connect"))
    )
    (net (code "108") (name "unconnected-(SW1-Pad1)") (class "Default")
      (node (ref "SW1") (pin "1") (pinfunction "1_1") (pintype "unspecified"))
    )
    (net (code "109") (name "unconnected-(SW1-Pad2)") (class "Default")
      (node (ref "SW1") (pin "2") (pinfunction "2_2") (pintype "unspecified"))
    )
    (net (code "110") (name "unconnected-(SW1-PadA)") (class "Default")
      (node (ref "SW1") (pin "A") (pinfunction "A_A") (pintype "unspecified"))
    )
    (net (code "111") (name "unconnected-(SW1-PadB)") (class "Default")
      (node (ref "SW1") (pin "B") (pinfunction "B_B") (pintype "unspecified"))
    )
    (net (code "112") (name "unconnected-(SW1-PadC)") (class "Default")
      (node (ref "SW1") (pin "C") (pinfunction "C_C") (pintype "unspecified"))
    )
    (net (code "113") (name "unconnected-(SW1-PadMT1)") (class "Default")
      (node (ref "SW1") (pin "MT1") (pinfunction "MT1_MT1") (pintype "unspecified"))
    )
    (net (code "114") (name "unconnected-(SW1-PadMT2)") (class "Default")
      (node (ref "SW1") (pin "MT2") (pinfunction "MT2_MT2") (pintype "unspecified"))
    )
    (net (code "115") (name "unconnected-(SW2-Pad1)") (class "Default")
      (node (ref "SW2") (pin "1") (pinfunction "1_1") (pintype "unspecified"))
    )
    (net (code "116") (name "unconnected-(SW2-Pad2)") (class "Default")
      (node (ref "SW2") (pin "2") (pinfunction "2_2") (pintype "unspecified"))
    )
    (net (code "117") (name "unconnected-(SW2-PadA)") (class "Default")
      (node (ref "SW2") (pin "A") (pinfunction "A_A") (pintype "unspecified"))
    )
    (net (code "118") (name "unconnected-(SW2-PadB)") (class "Default")
      (node (ref "SW2") (pin "B") (pinfunction "B_B") (pintype "unspecified"))
    )
    (net (code "119") (name "unconnected-(SW2-PadC)") (class "Default")
      (node (ref "SW2") (pin "C") (pinfunction "C_C") (pintype "unspecified"))
    )
    (net (code "120") (name "unconnected-(SW2-PadMT1)") (class "Default")
      (node (ref "SW2") (pin "MT1") (pinfunction "MT1_MT1") (pintype "unspecified"))
    )
    (net (code "121") (name "unconnected-(SW2-PadMT2)") (class "Default")
      (node (ref "SW2") (pin "MT2") (pinfunction "MT2_MT2") (pintype "unspecified"))
    )
    (net (code "122") (name "unconnected-(SW3-Pad1)") (class "Default")
      (node (ref "SW3") (pin "1") (pinfunction "1_1") (pintype "unspecified"))
    )
    (net (code "123") (name "unconnected-(SW3-Pad2)") (class "Default")
      (node (ref "SW3") (pin "2") (pinfunction "2_2") (pintype "unspecified"))
    )
    (net (code "124") (name "unconnected-(SW3-PadA)") (class "Default")
      (node (ref "SW3") (pin "A") (pinfunction "A_A") (pintype "unspecified"))
    )
    (net (code "125") (name "unconnected-(SW3-PadB)") (class "Default")
      (node (ref "SW3") (pin "B") (pinfunction "B_B") (pintype "unspecified"))
    )
    (net (code "126") (name "unconnected-(SW3-PadC)") (class "Default")
      (node (ref "SW3") (pin "C") (pinfunction "C_C") (pintype "unspecified"))
    )
    (net (code "127") (name "unconnected-(SW3-PadMT1)") (class "Default")
      (node (ref "SW3") (pin "MT1") (pinfunction "MT1_MT1") (pintype "unspecified"))
    )
    (net (code "128") (name "unconnected-(SW3-PadMT2)") (class "Default")
      (node (ref "SW3") (pin "MT2") (pinfunction "MT2_MT2") (pintype "unspecified"))
    )
    (net (code "129") (name "unconnected-(U1-Pad1)") (class "Default")
      (node (ref "U1") (pin "1") (pinfunction "1_1") (pintype "unspecified"))
    )
    (net (code "130") (name "unconnected-(U1-Pad2)") (class "Default")
      (node (ref "U1") (pin "2") (pinfunction "2_2") (pintype "unspecified"))
    )
    (net (code "131") (name "unconnected-(U1-Pad3)") (class "Default")
      (node (ref "U1") (pin "3") (pinfunction "3_3") (pintype "unspecified"))
    )
    (net (code "132") (name "unconnected-(U2-A0-Pad15)") (class "Default")
      (node (ref "U2") (pin "15") (pinfunction "A0_15") (pintype "unspecified"))
    )
    (net (code "133") (name "unconnected-(U2-A1-Pad16)") (class "Default")
      (node (ref "U2") (pin "16") (pinfunction "A1_16") (pintype "unspecified"))
    )
    (net (code "134") (name "unconnected-(U2-A2-Pad17)") (class "Default")
      (node (ref "U2") (pin "17") (pinfunction "A2_17") (pintype "unspecified"))
    )
    (net (code "135") (name "unconnected-(U2-CS#-Pad11)") (class "Default")
      (node (ref "U2") (pin "11") (pinfunction "CS#_11") (pintype "unspecified"))
    )
    (net (code "136") (name "unconnected-(U2-GPA0-Pad21)") (class "Default")
      (node (ref "U2") (pin "21") (pinfunction "GPA0_21") (pintype "bidirectional"))
    )
    (net (code "137") (name "unconnected-(U2-GPA1-Pad22)") (class "Default")
      (node (ref "U2") (pin "22") (pinfunction "GPA1_22") (pintype "bidirectional"))
    )
    (net (code "138") (name "unconnected-(U2-GPA2-Pad23)") (class "Default")
      (node (ref "U2") (pin "23") (pinfunction "GPA2_23") (pintype "bidirectional"))
    )
    (net (code "139") (name "unconnected-(U2-GPA3-Pad24)") (class "Default")
      (node (ref "U2") (pin "24") (pinfunction "GPA3_24") (pintype "bidirectional"))
    )
    (net (code "140") (name "unconnected-(U2-GPA4-Pad25)") (class "Default")
      (node (ref "U2") (pin "25") (pinfunction "GPA4_25") (pintype "bidirectional"))
    )
    (net (code "141") (name "unconnected-(U2-GPA5-Pad26)") (class "Default")
      (node (ref "U2") (pin "26") (pinfunction "GPA5_26") (pintype "bidirectional"))
    )
    (net (code "142") (name "unconnected-(U2-GPA6-Pad27)") (class "Default")
      (node (ref "U2") (pin "27") (pinfunction "GPA6_27") (pintype "bidirectional"))
    )
    (net (code "143") (name "unconnected-(U2-GPA7-Pad28)") (class "Default")
      (node (ref "U2") (pin "28") (pinfunction "GPA7_28") (pintype "bidirectional"))
    )
    (net (code "144") (name "unconnected-(U2-GPB0-Pad1)") (class "Default")
      (node (ref "U2") (pin "1") (pinfunction "GPB0_1") (pintype "bidirectional"))
    )
    (net (code "145") (name "unconnected-(U2-GPB1-Pad2)") (class "Default")
      (node (ref "U2") (pin "2") (pinfunction "GPB1_2") (pintype "bidirectional"))
    )
    (net (code "146") (name "unconnected-(U2-GPB2-Pad3)") (class "Default")
      (node (ref "U2") (pin "3") (pinfunction "GPB2_3") (pintype "bidirectional"))
    )
    (net (code "147") (name "unconnected-(U2-GPB3-Pad4)") (class "Default")
      (node (ref "U2") (pin "4") (pinfunction "GPB3_4") (pintype "bidirectional"))
    )
    (net (code "148") (name "unconnected-(U2-GPB4-Pad5)") (class "Default")
      (node (ref "U2") (pin "5") (pinfunction "GPB4_5") (pintype "bidirectional"))
    )
    (net (code "149") (name "unconnected-(U2-GPB5-Pad6)") (class "Default")
      (node (ref "U2") (pin "6") (pinfunction "GPB5_6") (pintype "bidirectional"))
    )
    (net (code "150") (name "unconnected-(U2-GPB6-Pad7)") (class "Default")
      (node (ref "U2") (pin "7") (pinfunction "GPB6_7") (pintype "bidirectional"))
    )
    (net (code "151") (name "unconnected-(U2-GPB7-Pad8)") (class "Default")
      (node (ref "U2") (pin "8") (pinfunction "GPB7_8") (pintype "bidirectional"))
    )
    (net (code "152") (name "unconnected-(U2-INTA-Pad20)") (class "Default")
      (node (ref "U2") (pin "20") (pinfunction "INTA_20") (pintype "unspecified"))
    )
    (net (code "153") (name "unconnected-(U2-INTB-Pad19)") (class "Default")
      (node (ref "U2") (pin "19") (pinfunction "INTB_19") (pintype "unspecified"))
    )
    (net (code "154") (name "unconnected-(U3-A0-Pad15)") (class "Default")
      (node (ref "U3") (pin "15") (pinfunction "A0_15") (pintype "unspecified"))
    )
    (net (code "155") (name "unconnected-(U3-A1-Pad16)") (class "Default")
      (node (ref "U3") (pin "16") (pinfunction "A1_16") (pintype "unspecified"))
    )
    (net (code "156") (name "unconnected-(U3-A2-Pad17)") (class "Default")
      (node (ref "U3") (pin "17") (pinfunction "A2_17") (pintype "unspecified"))
    )
    (net (code "157") (name "unconnected-(U3-CS#-Pad11)") (class "Default")
      (node (ref "U3") (pin "11") (pinfunction "CS#_11") (pintype "unspecified"))
    )
    (net (code "158") (name "unconnected-(U3-GPA0-Pad21)") (class "Default")
      (node (ref "U3") (pin "21") (pinfunction "GPA0_21") (pintype "bidirectional"))
    )
    (net (code "159") (name "unconnected-(U3-GPA1-Pad22)") (class "Default")
      (node (ref "U3") (pin "22") (pinfunction "GPA1_22") (pintype "bidirectional"))
    )
    (net (code "160") (name "unconnected-(U3-GPA2-Pad23)") (class "Default")
      (node (ref "U3") (pin "23") (pinfunction "GPA2_23") (pintype "bidirectional"))
    )
    (net (code "161") (name "unconnected-(U3-GPA3-Pad24)") (class "Default")
      (node (ref "U3") (pin "24") (pinfunction "GPA3_24") (pintype "bidirectional"))
    )
    (net (code "162") (name "unconnected-(U3-GPA4-Pad25)") (class "Default")
      (node (ref "U3") (pin "25") (pinfunction "GPA4_25") (pintype "bidirectional"))
    )
    (net (code "163") (name "unconnected-(U3-GPA5-Pad26)") (class "Default")
      (node (ref "U3") (pin "26") (pinfunction "GPA5_26") (pintype "bidirectional"))
    )
    (net (code "164") (name "unconnected-(U3-GPA6-Pad27)") (class "Default")
      (node (ref "U3") (pin "27") (pinfunction "GPA6_27") (pintype "bidirectional"))
    )
    (net (code "165") (name "unconnected-(U3-GPA7-Pad28)") (class "Default")
      (node (ref "U3") (pin "28") (pinfunction "GPA7_28") (pintype "bidirectional"))
    )
    (net (code "166") (name "unconnected-(U3-GPB0-Pad1)") (class "Default")
      (node (ref "U3") (pin "1") (pinfunction "GPB0_1") (pintype "bidirectional"))
    )
    (net (code "167") (name "unconnected-(U3-GPB1-Pad2)") (class "Default")
      (node (ref "U3") (pin "2") (pinfunction "GPB1_2") (pintype "bidirectional"))
    )
    (net (code "168") (name "unconnected-(U3-GPB2-Pad3)") (class "Default")
      (node (ref "U3") (pin "3") (pinfunction "GPB2_3") (pintype "bidirectional"))
    )
    (net (code "169") (name "unconnected-(U3-GPB3-Pad4)") (class "Default")
      (node (ref "U3") (pin "4") (pinfunction "GPB3_4") (pintype "bidirectional"))
    )
    (net (code "170") (name "unconnected-(U3-GPB4-Pad5)") (class "Default")
      (node (ref "U3") (pin "5") (pinfunction "GPB4_5") (pintype "bidirectional"))
    )
    (net (code "171") (name "unconnected-(U3-GPB5-Pad6)") (class "Default")
      (node (ref "U3") (pin "6") (pinfunction "GPB5_6") (pintype "bidirectional"))
    )
    (net (code "172") (name "unconnected-(U3-GPB6-Pad7)") (class "Default")
      (node (ref "U3") (pin "7") (pinfunction "GPB6_7") (pintype "bidirectional"))
    )
    (net (code "173") (name "unconnected-(U3-GPB7-Pad8)") (class "Default")
      (node (ref "U3") (pin "8") (pinfunction "GPB7_8") (pintype "bidirectional"))
    )
    (net (code "174") (name "unconnected-(U3-INTA-Pad20)") (class "Default")
      (node (ref "U3") (pin "20") (pinfunction "INTA_20") (pintype "unspecified"))
    )
    (net (code "175") (name "unconnected-(U3-INTB-Pad19)") (class "Default")
      (node (ref "U3") (pin "19") (pinfunction "INTB_19") (pintype "unspecified"))
    )
    (net (code "176") (name "unconnected-(U4-A0-Pad15)") (class "Default")
      (node (ref "U4") (pin "15") (pinfunction "A0_15") (pintype "unspecified"))
    )
    (net (code "177") (name "unconnected-(U4-A1-Pad16)") (class "Default")
      (node (ref "U4") (pin "16") (pinfunction "A1_16") (pintype "unspecified"))
    )
    (net (code "178") (name "unconnected-(U4-A2-Pad17)") (class "Default")
      (node (ref "U4") (pin "17") (pinfunction "A2_17") (pintype "unspecified"))
    )
    (net (code "179") (name "unconnected-(U4-CS#-Pad11)") (class "Default")
      (node (ref "U4") (pin "11") (pinfunction "CS#_11") (pintype "unspecified"))
    )
    (net (code "180") (name "unconnected-(U4-GPA0-Pad21)") (class "Default")
      (node (ref "U4") (pin "21") (pinfunction "GPA0_21") (pintype "bidirectional"))
    )
    (net (code "181") (name "unconnected-(U4-GPA1-Pad22)") (class "Default")
      (node (ref "U4") (pin "22") (pinfunction "GPA1_22") (pintype "bidirectional"))
    )
    (net (code "182") (name "unconnected-(U4-GPA2-Pad23)") (class "Default")
      (node (ref "U4") (pin "23") (pinfunction "GPA2_23") (pintype "bidirectional"))
    )
    (net (code "183") (name "unconnected-(U4-GPA3-Pad24)") (class "Default")
      (node (ref "U4") (pin "24") (pinfunction "GPA3_24") (pintype "bidirectional"))
    )
    (net (code "184") (name "unconnected-(U4-GPA4-Pad25)") (class "Default")
      (node (ref "U4") (pin "25") (pinfunction "GPA4_25") (pintype "bidirectional"))
    )
    (net (code "185") (name "unconnected-(U4-GPA5-Pad26)") (class "Default")
      (node (ref "U4") (pin "26") (pinfunction "GPA5_26") (pintype "bidirectional"))
    )
    (net (code "186") (name "unconnected-(U4-GPA6-Pad27)") (class "Default")
      (node (ref "U4") (pin "27") (pinfunction "GPA6_27") (pintype "bidirectional"))
    )
    (net (code "187") (name "unconnected-(U4-GPA7-Pad28)") (class "Default")
      (node (ref "U4") (pin "28") (pinfunction "GPA7_28") (pintype "bidirectional"))
    )
    (net (code "188") (name "unconnected-(U4-GPB0-Pad1)") (class "Default")
      (node (ref "U4") (pin "1") (pinfunction "GPB0_1") (pintype "bidirectional"))
    )
    (net (code "189") (name "unconnected-(U4-GPB1-Pad2)") (class "Default")
      (node (ref "U4") (pin "2") (pinfunction "GPB1_2") (pintype "bidirectional"))
    )
    (net (code "190") (name "unconnected-(U4-GPB2-Pad3)") (class "Default")
      (node (ref "U4") (pin "3") (pinfunction "GPB2_3") (pintype "bidirectional"))
    )
    (net (code "191") (name "unconnected-(U4-GPB3-Pad4)") (class "Default")
      (node (ref "U4") (pin "4") (pinfunction "GPB3_4") (pintype "bidirectional"))
    )
    (net (code "192") (name "unconnected-(U4-GPB4-Pad5)") (class "Default")
      (node (ref "U4") (pin "5") (pinfunction "GPB4_5") (pintype "bidirectional"))
    )
    (net (code "193") (name "unconnected-(U4-GPB5-Pad6)") (class "Default")
      (node (ref "U4") (pin "6") (pinfunction "GPB5_6") (pintype "bidirectional"))
    )
    (net (code "194") (name "unconnected-(U4-GPB6-Pad7)") (class "Default")
      (node (ref "U4") (pin "7") (pinfunction "GPB6_7") (pintype "bidirectional"))
    )
    (net (code "195") (name "unconnected-(U4-GPB7-Pad8)") (class "Default")
      (node (ref "U4") (pin "8") (pinfunction "GPB7_8") (pintype "bidirectional"))
    )
    (net (code "196") (name "unconnected-(U4-INTA-Pad20)") (class "Default")
      (node (ref "U4") (pin "20") (pinfunction "INTA_20") (pintype "unspecified"))
    )
    (net (code "197") (name "unconnected-(U4-INTB-Pad19)") (class "Default")
      (node (ref "U4") (pin "19") (pinfunction "INTB_19") (pintype "unspecified"))
    )
    (net (code "198") (name "unconnected-(U5-A0-Pad15)") (class "Default")
      (node (ref "U5") (pin "15") (pinfunction "A0_15") (pintype "unspecified"))
    )
    (net (code "199") (name "unconnected-(U5-A1-Pad16)") (class "Default")
      (node (ref "U5") (pin "16") (pinfunction "A1_16") (pintype "unspecified"))
    )
    (net (code "200") (name "unconnected-(U5-A2-Pad17)") (class "Default")
      (node (ref "U5") (pin "17") (pinfunction "A2_17") (pintype "unspecified"))
    )
    (net (code "201") (name "unconnected-(U5-CS#-Pad11)") (class "Default")
      (node (ref "U5") (pin "11") (pinfunction "CS#_11") (pintype "unspecified"))
    )
    (net (code "202") (name "unconnected-(U5-GPA0-Pad21)") (class "Default")
      (node (ref "U5") (pin "21") (pinfunction "GPA0_21") (pintype "bidirectional"))
    )
    (net (code "203") (name "unconnected-(U5-GPA1-Pad22)") (class "Default")
      (node (ref "U5") (pin "22") (pinfunction "GPA1_22") (pintype "bidirectional"))
    )
    (net (code "204") (name "unconnected-(U5-GPA2-Pad23)") (class "Default")
      (node (ref "U5") (pin "23") (pinfunction "GPA2_23") (pintype "bidirectional"))
    )
    (net (code "205") (name "unconnected-(U5-GPA3-Pad24)") (class "Default")
      (node (ref "U5") (pin "24") (pinfunction "GPA3_24") (pintype "bidirectional"))
    )
    (net (code "206") (name "unconnected-(U5-GPA4-Pad25)") (class "Default")
      (node (ref "U5") (pin "25") (pinfunction "GPA4_25") (pintype "bidirectional"))
    )
    (net (code "207") (name "unconnected-(U5-GPA5-Pad26)") (class "Default")
      (node (ref "U5") (pin "26") (pinfunction "GPA5_26") (pintype "bidirectional"))
    )
    (net (code "208") (name "unconnected-(U5-GPA6-Pad27)") (class "Default")
      (node (ref "U5") (pin "27") (pinfunction "GPA6_27") (pintype "bidirectional"))
    )
    (net (code "209") (name "unconnected-(U5-GPA7-Pad28)") (class "Default")
      (node (ref "U5") (pin "28") (pinfunction "GPA7_28") (pintype "bidirectional"))
    )
    (net (code "210") (name "unconnected-(U5-GPB0-Pad1)") (class "Default")
      (node (ref "U5") (pin "1") (pinfunction "GPB0_1") (pintype "bidirectional"))
    )
    (net (code "211") (name "unconnected-(U5-GPB1-Pad2)") (class "Default")
      (node (ref "U5") (pin "2") (pinfunction "GPB1_2") (pintype "bidirectional"))
    )
    (net (code "212") (name "unconnected-(U5-GPB2-Pad3)") (class "Default")
      (node (ref "U5") (pin "3") (pinfunction "GPB2_3") (pintype "bidirectional"))
    )
    (net (code "213") (name "unconnected-(U5-GPB3-Pad4)") (class "Default")
      (node (ref "U5") (pin "4") (pinfunction "GPB3_4") (pintype "bidirectional"))
    )
    (net (code "214") (name "unconnected-(U5-GPB4-Pad5)") (class "Default")
      (node (ref "U5") (pin "5") (pinfunction "GPB4_5") (pintype "bidirectional"))
    )
    (net (code "215") (name "unconnected-(U5-GPB5-Pad6)") (class "Default")
      (node (ref "U5") (pin "6") (pinfunction "GPB5_6") (pintype "bidirectional"))
    )
    (net (code "216") (name "unconnected-(U5-GPB6-Pad7)") (class "Default")
      (node (ref "U5") (pin "7") (pinfunction "GPB6_7") (pintype "bidirectional"))
    )
    (net (code "217") (name "unconnected-(U5-GPB7-Pad8)") (class "Default")
      (node (ref "U5") (pin "8") (pinfunction "GPB7_8") (pintype "bidirectional"))
    )
    (net (code "218") (name "unconnected-(U5-INTA-Pad20)") (class "Default")
      (node (ref "U5") (pin "20") (pinfunction "INTA_20") (pintype "unspecified"))
    )
    (net (code "219") (name "unconnected-(U5-INTB-Pad19)") (class "Default")
      (node (ref "U5") (pin "19") (pinfunction "INTB_19") (pintype "unspecified"))
    )
    (net (code "220") (name "unconnected-(U6-Pad1)") (class "Default")
      (node (ref "U6") (pin "1") (pinfunction "1_1") (pintype "unspecified"))
    )
    (net (code "221") (name "unconnected-(U6-Pad2)") (class "Default")
      (node (ref "U6") (pin "2") (pinfunction "2_2") (pintype "unspecified"))
    )
    (net (code "222") (name "unconnected-(U6-Pad3)") (class "Default")
      (node (ref "U6") (pin "3") (pinfunction "3_3") (pintype "unspecified"))
    )
    (net (code "223") (name "unconnected-(U7-Pad1)") (class "Default")
      (node (ref "U7") (pin "1") (pinfunction "1_1") (pintype "unspecified"))
    )
    (net (code "224") (name "unconnected-(U7-Pad2)") (class "Default")
      (node (ref "U7") (pin "2") (pinfunction "2_2") (pintype "unspecified"))
    )
  )
)
